# DC_Pump_Soft_Starter.net
KiCad netlist of a schematic drawn in Altium Designer
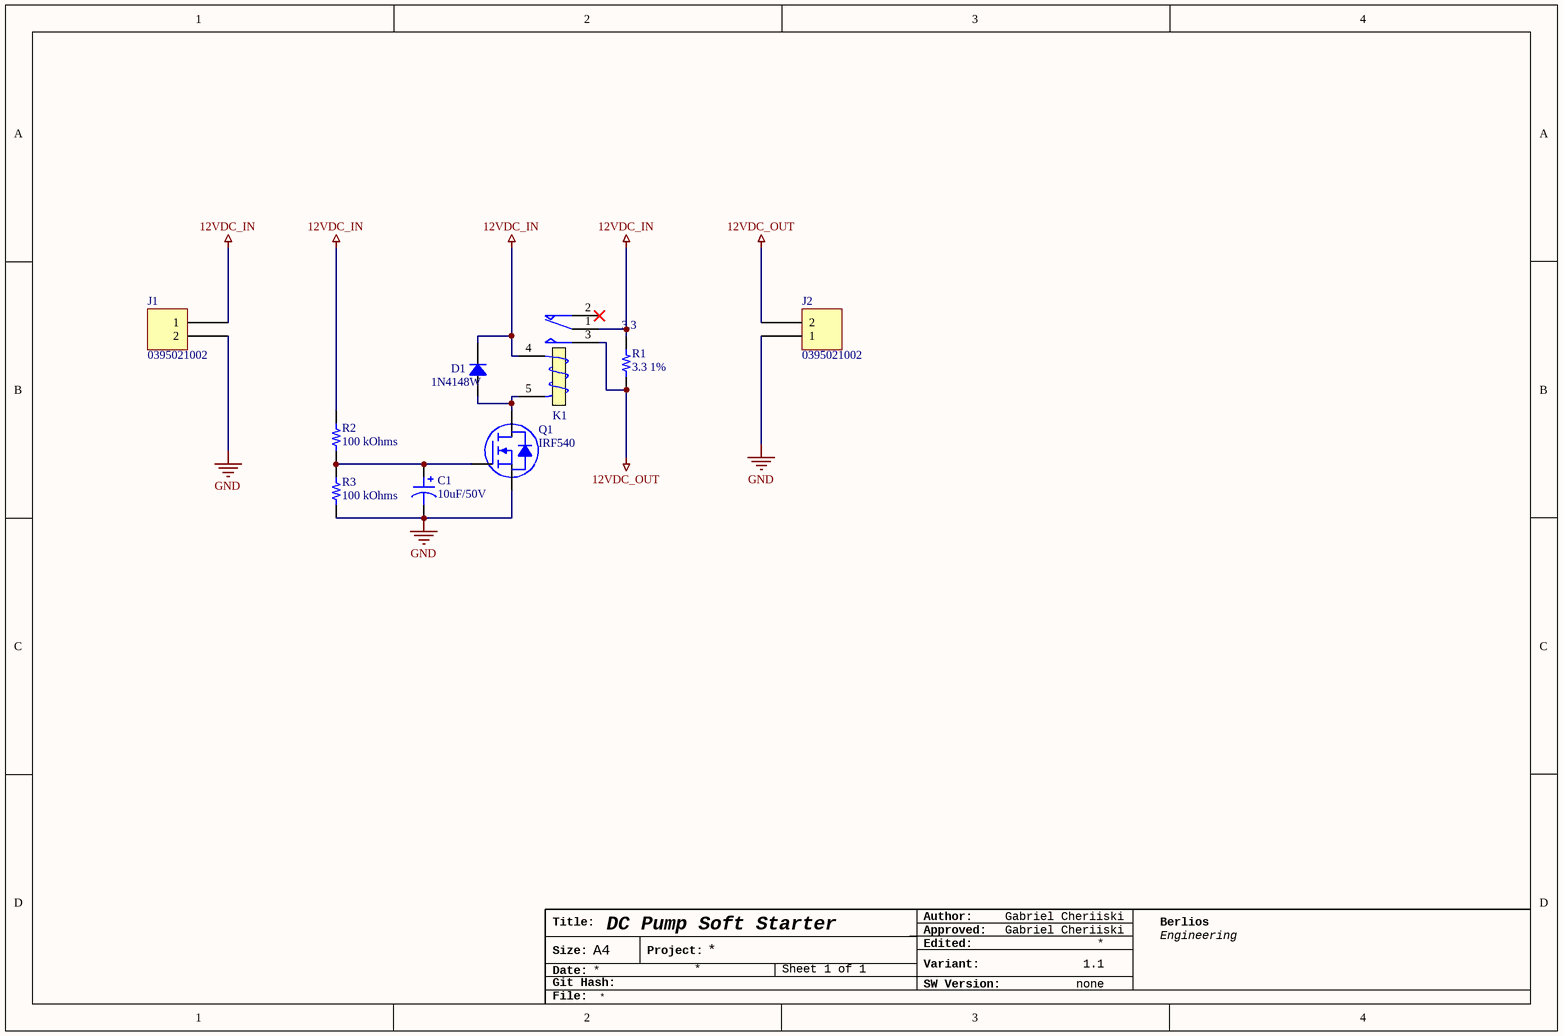
[diagram p0: DC_Pump_Soft_Starter.SchDoc]

(export (version "E")
  (design (tool "Eeschema 10.0.6"))
  (components
    (comp (ref "C1")
      (value "10uF/50V")
      (footprint "CAP TH ALUM ELEC D6.30mm S2.50mm H8.00mm")
      (description "CAP ALUM 10UF 20% 50V THRU HOLE")
      (fields (field (name "PART NUMBER") "106RSS050M") (field (name "MANUFACTURER") "Illinois Capacitor"))
      (libsource (lib "Capacitors - Aluminum - Electrolytic TH") (part "106RSS050M"))
    )
    (comp (ref "D1")
      (value "1N4148W")
      (footprint "SOD123F")
      (description "SOD-123 SMD")
      (fields (field (name "MANUFACTURER") "SMC Diode Solutions"))
      (libsource (lib "Diodes - Rectifiers - Single") (part "1N4007FLTR"))
    )
    (comp (ref "J1")
      (value "0395021002")
      (footprint "MOLEX 395021002")
      (description "TERM BLOCK HDR 2POS 90DEG 3.5MM")
      (fields (field (name "MANUFACTURER") "Molex"))
      (libsource (lib "Connectors - Terminal Blocks - Headers Plugs and Sockets") (part "0395021002"))
    )
    (comp (ref "J2")
      (value "0395021002")
      (footprint "MOLEX 395021002")
      (description "TERM BLOCK HDR 2POS 90DEG 3.5MM")
      (fields (field (name "MANUFACTURER") "Molex"))
      (libsource (lib "") (part "0395021002_1"))
    )
    (comp (ref "K1")
      (value "Relay 5pin Mini Milon 12V")
      (footprint "REL_MILON_MINI")
      (description "TRKM S-Z L 12VDC")
      (fields (field (name "PARTNUMBER") "TRKM S-Z L12VDC"))
      (libsource (lib "Relay") (part "Relay 5pin Mini Milon 12V"))
    )
    (comp (ref "Q1")
      (value "IRF540")
      (footprint "TO-220-3")
      (description "N-Channel 100V 33A (Tc) 94W (Tc) Through Hole TO-220AB")
      (libsource (lib "Transistor") (part "IRFZ44 (THD)"))
    )
    (comp (ref "R1")
      (value "3.3 1%")
      (footprint "RES TH 2W AXIAL-0.8")
      (description "TH Resistor")
      (fields (field (name "ALTIUM_VALUE") "3.3"))
      (libsource (lib "Resistor") (part "Res TH 2W AXIAL-0.8"))
    )
    (comp (ref "R2")
      (value "100 kOhms")
      (footprint "RES 0805_2012")
      (description "RESHIGHPOWERA 0805 100K 1% 1/2W")
      (fields (field (name "PART NUMBER") "CHP0805AFX-1003ELF") (field (name "MANUFACTURER") "Bourns Inc."))
      (libsource (lib "Resistors - Surface Mount - 0805") (part "CHP0805AFX-1003ELF"))
    )
    (comp (ref "R3")
      (value "100 kOhms")
      (footprint "RES 0805_2012")
      (description "RESHIGHPOWERA 0805 100K 1% 1/2W")
      (fields (field (name "PART NUMBER") "CHP0805AFX-1003ELF") (field (name "MANUFACTURER") "Bourns Inc."))
      (libsource (lib "Resistors - Surface Mount - 0805") (part "CHP0805AFX-1003ELF"))
    )
  )
  (nets
    (net (code "1") (name "12VDC_IN") (class "Default")
      (node (ref "D1") (pin "2") (pinfunction "2_2") (pintype "passive"))
      (node (ref "J1") (pin "1") (pinfunction "1_1") (pintype "passive"))
      (node (ref "K1") (pin "1") (pinfunction "COM_1") (pintype "passive"))
      (node (ref "K1") (pin "4") (pinfunction "T1_4") (pintype "passive"))
      (node (ref "R1") (pin "1") (pinfunction "1_1") (pintype "passive"))
      (node (ref "R2") (pin "2") (pinfunction "2_2") (pintype "passive"))
    )
    (net (code "2") (name "12VDC_OUT") (class "Default")
      (node (ref "J2") (pin "2") (pinfunction "2_2") (pintype "passive"))
      (node (ref "K1") (pin "3") (pinfunction "NO_3") (pintype "passive"))
      (node (ref "R1") (pin "2") (pinfunction "2_2") (pintype "passive"))
    )
    (net (code "3") (name "GND") (class "Default")
      (node (ref "C1") (pin "2") (pinfunction "2_2") (pintype "passive"))
      (node (ref "J1") (pin "2") (pinfunction "2_2") (pintype "passive"))
      (node (ref "J2") (pin "1") (pinfunction "1_1") (pintype "passive"))
      (node (ref "Q1") (pin "3") (pinfunction "S_3") (pintype "passive"))
      (node (ref "R3") (pin "1") (pinfunction "1_1") (pintype "passive"))
    )
    (net (code "4") (name "Net-(K1-T2)") (class "Default")
      (node (ref "D1") (pin "1") (pinfunction "1_1") (pintype "passive"))
      (node (ref "K1") (pin "5") (pinfunction "T2_5") (pintype "passive"))
      (node (ref "Q1") (pin "2") (pinfunction "D_2") (pintype "passive"))
    )
    (net (code "5") (name "Net-(Q1-G)") (class "Default")
      (node (ref "C1") (pin "1") (pinfunction "1_1") (pintype "passive"))
      (node (ref "Q1") (pin "1") (pinfunction "G_1") (pintype "passive"))
      (node (ref "R2") (pin "1") (pinfunction "1_1") (pintype "passive"))
      (node (ref "R3") (pin "2") (pinfunction "2_2") (pintype "passive"))
    )
    (net (code "6") (name "unconnected-(K1-NC-Pad2)") (class "Default")
      (node (ref "K1") (pin "2") (pinfunction "NC_2") (pintype "passive+no_connect"))
    )
  )
)
